# 14_Clocks.net
KiCad netlist of a schematic drawn in Altium Designer
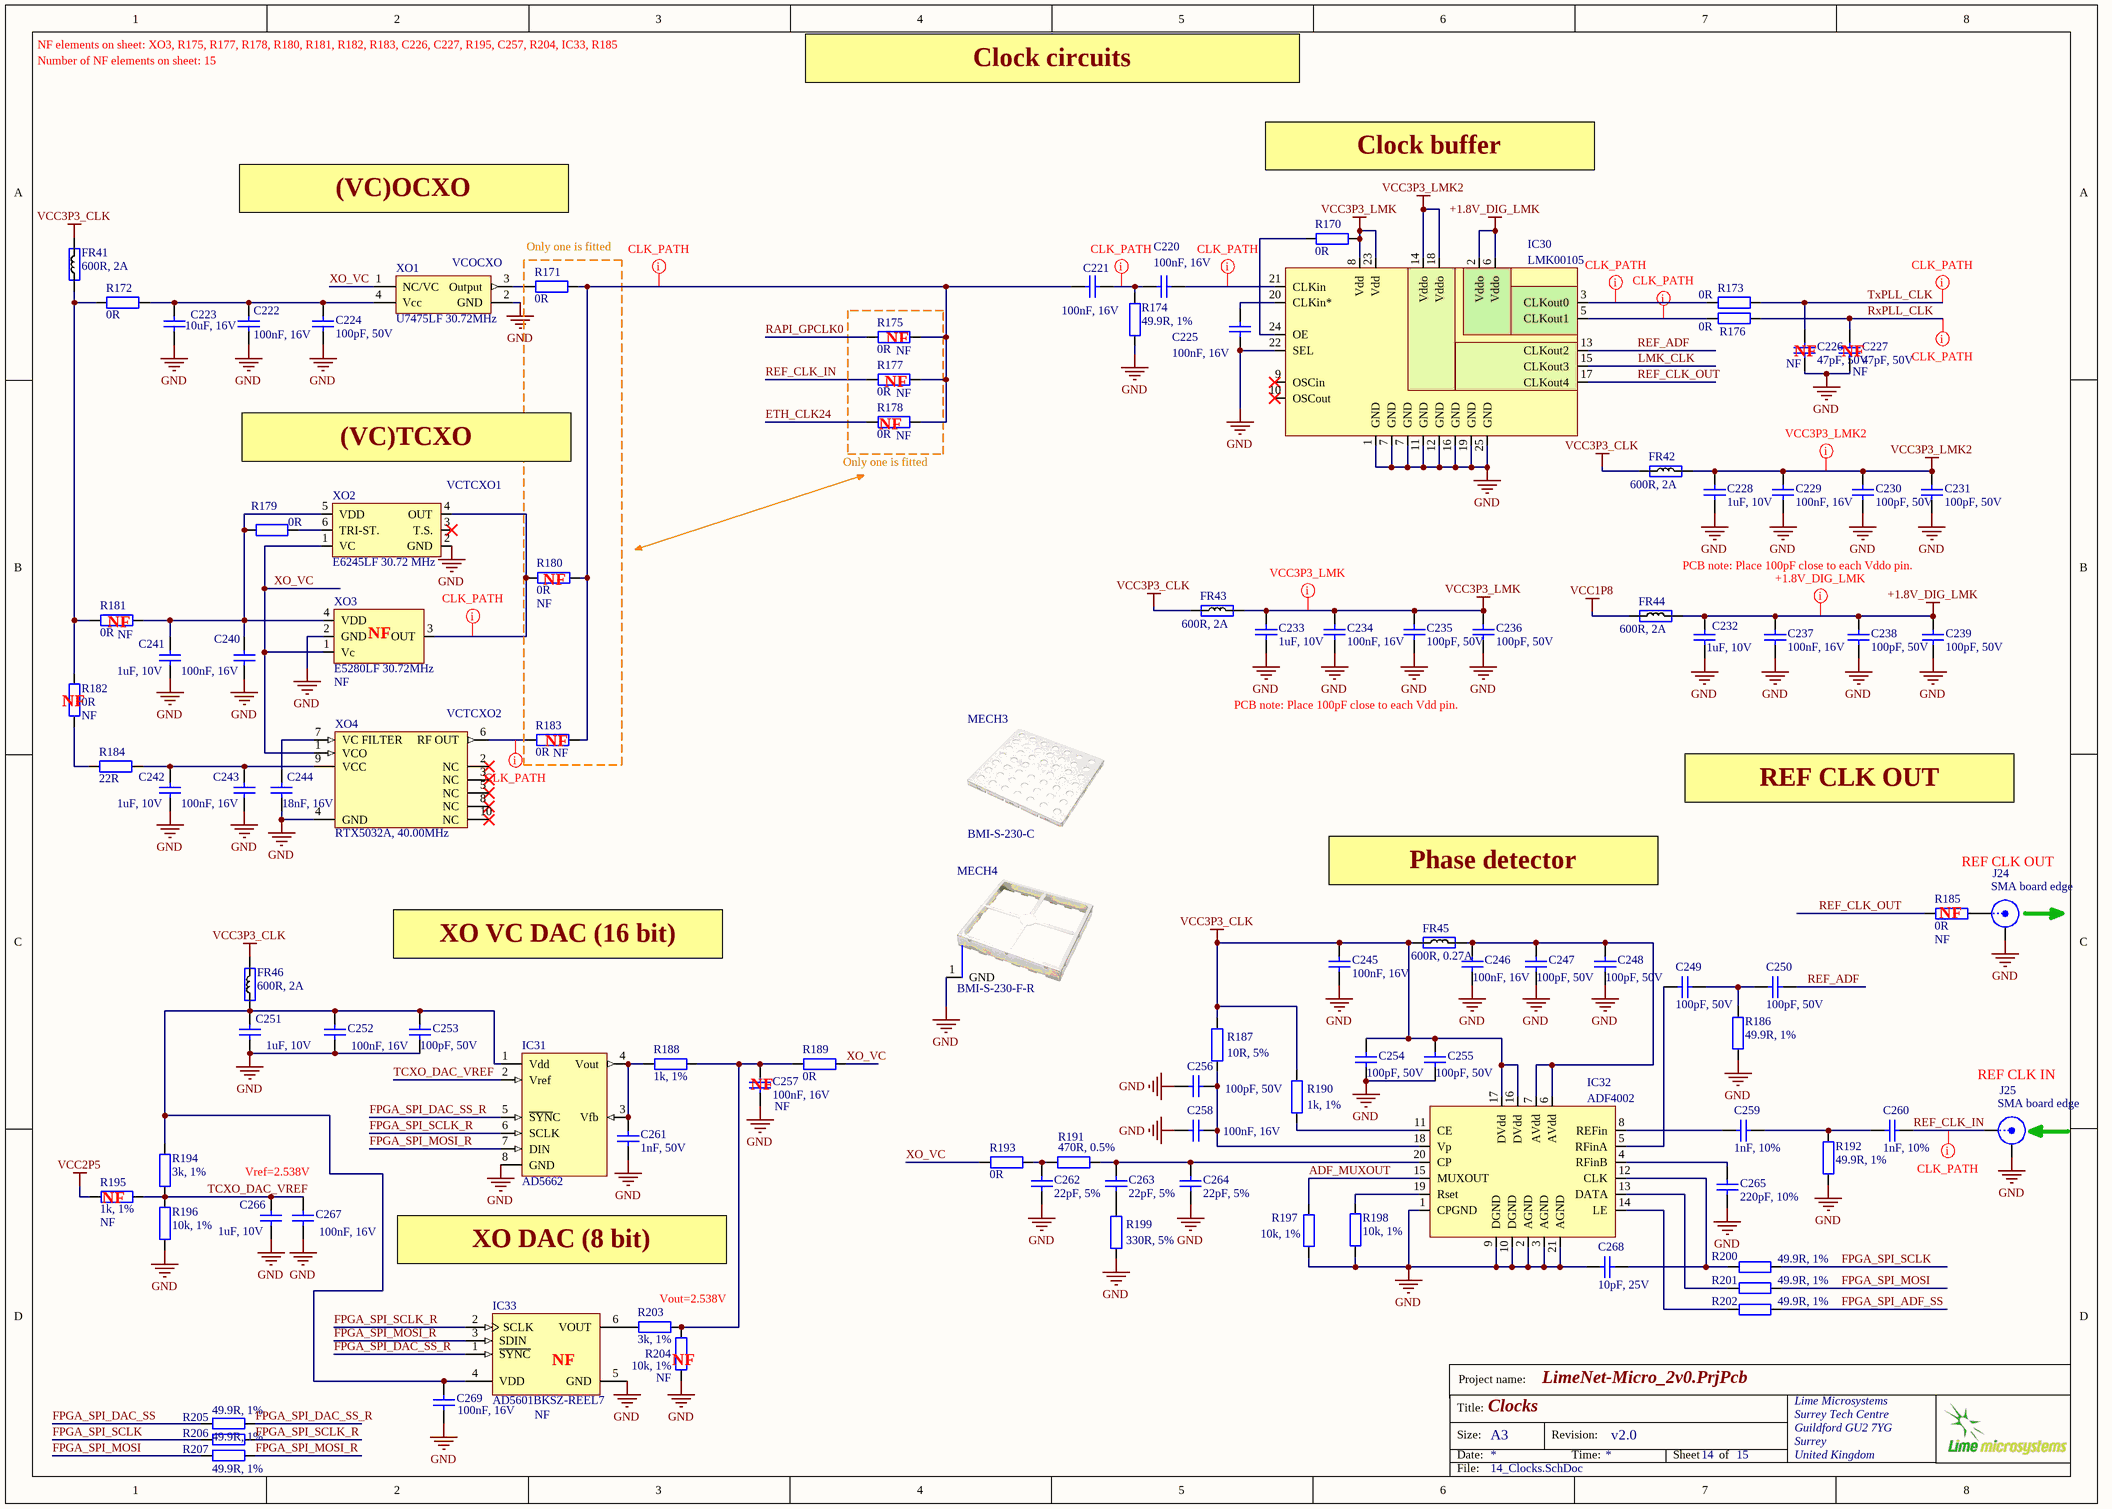
[diagram p0: 14_Clocks.SchDoc]

(export (version "E")
  (design (tool "Eeschema 10.0.6"))
  (components
    (comp (ref "C220")
      (value "100nF, 16V")
      (footprint "CAP0402")
      (fields
        (field (name "MANUFACTURER") "Murata Electronics")
        (field (name "TOLERANCE") "10 %")
        (field (name "MANUFACTURER PART NUMBER") "GRM155R71C104KA88D")
      )
      (libsource (lib "LimeMicroAltiumLib_schLib") (part "Cap_0402"))
    )
    (comp (ref "C221")
      (value "100nF, 16V")
      (footprint "CAP0402")
      (fields
        (field (name "MANUFACTURER") "Murata Electronics")
        (field (name "TOLERANCE") "10 %")
        (field (name "MANUFACTURER PART NUMBER") "GRM155R71C104KA88D")
      )
      (libsource (lib "LimeMicroAltiumLib_schLib") (part "Cap_0402"))
    )
    (comp (ref "C222")
      (value "100nF, 16V")
      (footprint "CAP0402")
      (fields
        (field (name "MANUFACTURER") "Murata Electronics")
        (field (name "TOLERANCE") "10 %")
        (field (name "MANUFACTURER PART NUMBER") "GRM155R71C104KA88D")
      )
      (libsource (lib "LimeMicroAltiumLib_schLib") (part "Cap_0402"))
    )
    (comp (ref "C223")
      (value "10uF, 16V")
      (footprint "CAP0603")
      (fields (field (name "MANUFACTURER") "Yageo") (field (name "TOLERANCE") "±20%"))
      (libsource (lib "LimeMicroAltiumLib_schLib") (part "Cap_0603"))
    )
    (comp (ref "C224")
      (value "100pF, 50V")
      (footprint "CAP0402")
      (fields (field (name "TOLERANCE") "±5%") (field (name "MANUFACTURER") "Yageo"))
      (libsource (lib "LimeMicroAltiumLib_schLib") (part "Cap_0402"))
    )
    (comp (ref "C225")
      (value "100nF, 16V")
      (footprint "CAP0402")
      (fields
        (field (name "MANUFACTURER") "Murata Electronics")
        (field (name "TOLERANCE") "10 %")
        (field (name "MANUFACTURER PART NUMBER") "GRM155R71C104KA88D")
      )
      (libsource (lib "LimeMicroAltiumLib_schLib") (part "Cap_0402"))
    )
    (comp (ref "C226")
      (value "47pF, 50V")
      (footprint "CAP0402")
      (fields
        (field (name "TOLERANCE") "±1%")
        (field (name "MANUFACTURER") "TDK Corporation")
        (field (name "ASSEMBLY INFO") "NF")
      )
      (libsource (lib "LimeMicroAltiumLib_schLib") (part "Cap_0402"))
    )
    (comp (ref "C227")
      (value "47pF, 50V")
      (footprint "CAP0402")
      (fields
        (field (name "TOLERANCE") "±1%")
        (field (name "MANUFACTURER") "TDK Corporation")
        (field (name "ASSEMBLY INFO") "NF")
      )
      (libsource (lib "LimeMicroAltiumLib_schLib") (part "Cap_0402"))
    )
    (comp (ref "C228")
      (value "1uF, 10V")
      (footprint "CAP0402")
      (description "CAP CER 1UF 10V X5R 0402")
      (fields
        (field (name "MANUFACTURER") "Yageo")
        (field (name "MANUFACTURER PART NUMBER") "CC0402MRX5R6BB105")
      )
      (libsource (lib "LimeMicroAltiumLib_schLib") (part "Cap_0402"))
    )
    (comp (ref "C229")
      (value "100nF, 16V")
      (footprint "CAP0402")
      (fields
        (field (name "MANUFACTURER") "Murata Electronics")
        (field (name "TOLERANCE") "10 %")
        (field (name "MANUFACTURER PART NUMBER") "GRM155R71C104KA88D")
      )
      (libsource (lib "LimeMicroAltiumLib_schLib") (part "Cap_0402"))
    )
    (comp (ref "C230")
      (value "100pF, 50V")
      (footprint "CAP0402")
      (fields (field (name "MANUFACTURER") "Yageo") (field (name "TOLERANCE") "±5%"))
      (libsource (lib "LimeMicroAltiumLib_schLib") (part "Cap_0402"))
    )
    (comp (ref "C231")
      (value "100pF, 50V")
      (footprint "CAP0402")
      (fields (field (name "MANUFACTURER") "Yageo") (field (name "TOLERANCE") "±5%"))
      (libsource (lib "LimeMicroAltiumLib_schLib") (part "Cap_0402"))
    )
    (comp (ref "C232")
      (value "1uF, 10V")
      (footprint "CAP0402")
      (description "CAP CER 1UF 10V X5R 0402")
      (fields
        (field (name "MANUFACTURER") "Yageo")
        (field (name "MANUFACTURER PART NUMBER") "CC0402MRX5R6BB105")
      )
      (libsource (lib "LimeMicroAltiumLib_schLib") (part "Cap_0402"))
    )
    (comp (ref "C233")
      (value "1uF, 10V")
      (footprint "CAP0402")
      (description "CAP CER 1UF 10V X5R 0402")
      (fields
        (field (name "MANUFACTURER") "Yageo")
        (field (name "MANUFACTURER PART NUMBER") "CC0402MRX5R6BB105")
      )
      (libsource (lib "LimeMicroAltiumLib_schLib") (part "Cap_0402"))
    )
    (comp (ref "C234")
      (value "100nF, 16V")
      (footprint "CAP0402")
      (fields
        (field (name "MANUFACTURER") "Murata Electronics")
        (field (name "TOLERANCE") "10 %")
        (field (name "MANUFACTURER PART NUMBER") "GRM155R71C104KA88D")
      )
      (libsource (lib "LimeMicroAltiumLib_schLib") (part "Cap_0402"))
    )
    (comp (ref "C235")
      (value "100pF, 50V")
      (footprint "CAP0402")
      (fields (field (name "MANUFACTURER") "Yageo") (field (name "TOLERANCE") "±5%"))
      (libsource (lib "LimeMicroAltiumLib_schLib") (part "Cap_0402"))
    )
    (comp (ref "C236")
      (value "100pF, 50V")
      (footprint "CAP0402")
      (fields (field (name "MANUFACTURER") "Yageo") (field (name "TOLERANCE") "±5%"))
      (libsource (lib "LimeMicroAltiumLib_schLib") (part "Cap_0402"))
    )
    (comp (ref "C237")
      (value "100nF, 16V")
      (footprint "CAP0402")
      (fields
        (field (name "MANUFACTURER") "Murata Electronics")
        (field (name "TOLERANCE") "10 %")
        (field (name "MANUFACTURER PART NUMBER") "GRM155R71C104KA88D")
      )
      (libsource (lib "LimeMicroAltiumLib_schLib") (part "Cap_0402"))
    )
    (comp (ref "C238")
      (value "100pF, 50V")
      (footprint "CAP0402")
      (fields (field (name "MANUFACTURER") "Yageo") (field (name "TOLERANCE") "±5%"))
      (libsource (lib "LimeMicroAltiumLib_schLib") (part "Cap_0402"))
    )
    (comp (ref "C239")
      (value "100pF, 50V")
      (footprint "CAP0402")
      (fields (field (name "MANUFACTURER") "Yageo") (field (name "TOLERANCE") "±5%"))
      (libsource (lib "LimeMicroAltiumLib_schLib") (part "Cap_0402"))
    )
    (comp (ref "C240")
      (value "100nF, 16V")
      (footprint "CAP0402")
      (fields
        (field (name "MANUFACTURER") "Murata Electronics")
        (field (name "TOLERANCE") "10 %")
        (field (name "MANUFACTURER PART NUMBER") "GRM155R71C104KA88D")
      )
      (libsource (lib "LimeMicroAltiumLib_schLib") (part "Cap_0402"))
    )
    (comp (ref "C241")
      (value "1uF, 10V")
      (footprint "CAP0402")
      (description "CAP CER 1UF 10V X5R 0402")
      (fields
        (field (name "MANUFACTURER") "Yageo")
        (field (name "MANUFACTURER PART NUMBER") "CC0402MRX5R6BB105")
      )
      (libsource (lib "LimeMicroAltiumLib_schLib") (part "Cap_0402"))
    )
    (comp (ref "C242")
      (value "1uF, 10V")
      (footprint "CAP0402")
      (description "CAP CER 1UF 10V X5R 0402")
      (fields
        (field (name "MANUFACTURER") "Yageo")
        (field (name "MANUFACTURER PART NUMBER") "CC0402MRX5R6BB105")
      )
      (libsource (lib "LimeMicroAltiumLib_schLib") (part "Cap_0402"))
    )
    (comp (ref "C243")
      (value "100nF, 16V")
      (footprint "CAP0402")
      (fields
        (field (name "MANUFACTURER") "Murata Electronics")
        (field (name "TOLERANCE") "10 %")
        (field (name "MANUFACTURER PART NUMBER") "GRM155R71C104KA88D")
      )
      (libsource (lib "LimeMicroAltiumLib_schLib") (part "Cap_0402"))
    )
    (comp (ref "C244")
      (value "18nF, 16V")
      (footprint "CAP0402")
      (fields (field (name "MANUFACTURER") "Yageo") (field (name "TOLERANCE") "±10%"))
      (libsource (lib "LimeMicroAltiumLib_schLib") (part "Cap_0402"))
    )
    (comp (ref "C245")
      (value "100nF, 16V")
      (footprint "CAP0402")
      (fields
        (field (name "MANUFACTURER") "Murata Electronics")
        (field (name "TOLERANCE") "10 %")
        (field (name "MANUFACTURER PART NUMBER") "GRM155R71C104KA88D")
      )
      (libsource (lib "LimeMicroAltiumLib_schLib") (part "Cap_0402"))
    )
    (comp (ref "C246")
      (value "100nF, 16V")
      (footprint "CAP0402")
      (fields
        (field (name "MANUFACTURER") "Murata Electronics")
        (field (name "TOLERANCE") "10 %")
        (field (name "MANUFACTURER PART NUMBER") "GRM155R71C104KA88D")
      )
      (libsource (lib "LimeMicroAltiumLib_schLib") (part "Cap_0402"))
    )
    (comp (ref "C247")
      (value "100pF, 50V")
      (footprint "CAP0402")
      (fields (field (name "MANUFACTURER") "Yageo") (field (name "TOLERANCE") "±5%"))
      (libsource (lib "LimeMicroAltiumLib_schLib") (part "Cap_0402"))
    )
    (comp (ref "C248")
      (value "100pF, 50V")
      (footprint "CAP0402")
      (fields (field (name "MANUFACTURER") "Yageo") (field (name "TOLERANCE") "±5%"))
      (libsource (lib "LimeMicroAltiumLib_schLib") (part "Cap_0402"))
    )
    (comp (ref "C249")
      (value "100pF, 50V")
      (footprint "CAP0402")
      (fields (field (name "MANUFACTURER") "Yageo") (field (name "TOLERANCE") "±5%"))
      (libsource (lib "LimeMicroAltiumLib_schLib") (part "Cap_0402"))
    )
    (comp (ref "C250")
      (value "100pF, 50V")
      (footprint "CAP0402")
      (fields (field (name "MANUFACTURER") "Yageo") (field (name "TOLERANCE") "±5%"))
      (libsource (lib "LimeMicroAltiumLib_schLib") (part "Cap_0402"))
    )
    (comp (ref "C251")
      (value "1uF, 10V")
      (footprint "CAP0402")
      (description "CAP CER 1UF 10V X5R 0402")
      (fields
        (field (name "MANUFACTURER") "Yageo")
        (field (name "MANUFACTURER PART NUMBER") "CC0402MRX5R6BB105")
      )
      (libsource (lib "LimeMicroAltiumLib_schLib") (part "Cap_0402"))
    )
    (comp (ref "C252")
      (value "100nF, 16V")
      (footprint "CAP0402")
      (fields
        (field (name "TOLERANCE") "10 %")
        (field (name "MANUFACTURER") "Murata Electronics")
        (field (name "MANUFACTURER PART NUMBER") "GRM155R71C104KA88D")
      )
      (libsource (lib "LimeFPGAboard_schLib") (part "Cap_0603"))
    )
    (comp (ref "C253")
      (value "100pF, 50V")
      (footprint "CAP0402")
      (fields (field (name "MANUFACTURER") "Yageo") (field (name "TOLERANCE") "±5%"))
      (libsource (lib "LimeMicroAltiumLib_schLib") (part "Cap_0402"))
    )
    (comp (ref "C254")
      (value "100pF, 50V")
      (footprint "CAP0402")
      (fields (field (name "MANUFACTURER") "Yageo") (field (name "TOLERANCE") "±5%"))
      (libsource (lib "LimeMicroAltiumLib_schLib") (part "Cap_0402"))
    )
    (comp (ref "C255")
      (value "100pF, 50V")
      (footprint "CAP0402")
      (fields (field (name "MANUFACTURER") "Yageo") (field (name "TOLERANCE") "±5%"))
      (libsource (lib "LimeMicroAltiumLib_schLib") (part "Cap_0402"))
    )
    (comp (ref "C256")
      (value "100pF, 50V")
      (footprint "CAP0402")
      (fields (field (name "MANUFACTURER") "Yageo") (field (name "TOLERANCE") "±5%"))
      (libsource (lib "LimeMicroAltiumLib_schLib") (part "Cap_0402"))
    )
    (comp (ref "C257")
      (value "100nF, 16V")
      (footprint "CAP0402")
      (fields
        (field (name "ASSEMBLY INFO") "NF")
        (field (name "MANUFACTURER") "Murata Electronics")
        (field (name "TOLERANCE") "10 %")
        (field (name "MANUFACTURER PART NUMBER") "GRM155R71C104KA88D")
      )
      (libsource (lib "LimeMicroAltiumLib_schLib") (part "Cap_0402"))
    )
    (comp (ref "C258")
      (value "100nF, 16V")
      (footprint "CAP0402")
      (fields
        (field (name "MANUFACTURER") "Murata Electronics")
        (field (name "TOLERANCE") "10 %")
        (field (name "MANUFACTURER PART NUMBER") "GRM155R71C104KA88D")
      )
      (libsource (lib "LimeMicroAltiumLib_schLib") (part "Cap_0402"))
    )
    (comp (ref "C259")
      (value "1nF, 10%")
      (footprint "CAP0402")
      (fields (field (name "TOLERANCE") "10 %") (field (name "MANUFACTURER") "Murata Electronics"))
      (libsource (lib "LimeMicroAltiumLib_schLib") (part "Cap_0402"))
    )
    (comp (ref "C260")
      (value "1nF, 10%")
      (footprint "CAP0402")
      (fields (field (name "TOLERANCE") "10 %") (field (name "MANUFACTURER") "Murata Electronics"))
      (libsource (lib "LimeMicroAltiumLib_schLib") (part "Cap_0402"))
    )
    (comp (ref "C261")
      (value "1nF, 50V")
      (footprint "CAP0402")
      (fields
        (field (name "TOLERANCE") "±10%")
        (field (name "MANUFACTURER") "Murata Electronics North America")
      )
      (libsource (lib "LimeMicroAltiumLib_schLib") (part "Cap_0402"))
    )
    (comp (ref "C262")
      (value "22pF, 5%")
      (footprint "CAP0402")
      (fields (field (name "TOLERANCE") "±5%") (field (name "MANUFACTURER") "Yageo"))
      (libsource (lib "LimeMicroAltiumLib_schLib") (part "Cap_0402"))
    )
    (comp (ref "C263")
      (value "22pF, 5%")
      (footprint "CAP0402")
      (fields (field (name "TOLERANCE") "±5%") (field (name "MANUFACTURER") "Yageo"))
      (libsource (lib "LimeMicroAltiumLib_schLib") (part "Cap_0402"))
    )
    (comp (ref "C264")
      (value "22pF, 5%")
      (footprint "CAP0402")
      (fields (field (name "TOLERANCE") "±5%") (field (name "MANUFACTURER") "Yageo"))
      (libsource (lib "LimeMicroAltiumLib_schLib") (part "Cap_0402"))
    )
    (comp (ref "C265")
      (value "220pF, 10%")
      (footprint "CAP0402")
      (fields (field (name "MANUFACTURER") "Yageo") (field (name "TOLERANCE") "±10%"))
      (libsource (lib "LimeMicroAltiumLib_schLib") (part "Cap_0402"))
    )
    (comp (ref "C266")
      (value "1uF, 10V")
      (footprint "CAP0402")
      (description "CAP CER 1UF 10V X5R 0402")
      (fields
        (field (name "MANUFACTURER") "Yageo")
        (field (name "MANUFACTURER PART NUMBER") "CC0402MRX5R6BB105")
      )
      (libsource (lib "LimeMicroAltiumLib_schLib") (part "Cap_0402"))
    )
    (comp (ref "C267")
      (value "100nF, 16V")
      (footprint "CAP0402")
      (fields
        (field (name "TOLERANCE") "10 %")
        (field (name "MANUFACTURER") "Murata Electronics")
        (field (name "MANUFACTURER PART NUMBER") "GRM155R71C104KA88D")
      )
      (libsource (lib "LimeFPGAboard_schLib") (part "Cap_0603"))
    )
    (comp (ref "C268")
      (value "10pF, 25V")
      (footprint "CAP0402")
      (fields (field (name "MANUFACTURER") "AVX"))
      (libsource (lib "LimeMicroAltiumLib_schLib") (part "Cap_0402"))
    )
    (comp (ref "C269")
      (value "100nF, 16V")
      (footprint "CAP0402")
      (fields
        (field (name "TOLERANCE") "10 %")
        (field (name "MANUFACTURER") "Murata Electronics")
        (field (name "MANUFACTURER PART NUMBER") "GRM155R71C104KA88D")
      )
      (libsource (lib "LimeFPGAboard_schLib") (part "Cap_0603"))
    )
    (comp (ref "FR41")
      (value "600R, 2A")
      (footprint "RES0805")
      (fields (field (name "MANUFACTURER") "TDK Corporation"))
      (libsource (lib "LimeFPGAboard_schLib") (part "Ferrite"))
    )
    (comp (ref "FR42")
      (value "600R, 2A")
      (footprint "RES0805")
      (fields (field (name "MANUFACTURER") "TDK Corporation"))
      (libsource (lib "LimeMicroAltiumLib_schLib") (part "Ferrite"))
    )
    (comp (ref "FR43")
      (value "600R, 2A")
      (footprint "RES0805")
      (fields (field (name "MANUFACTURER") "TDK Corporation"))
      (libsource (lib "LimeMicroAltiumLib_schLib") (part "Ferrite"))
    )
    (comp (ref "FR44")
      (value "600R, 2A")
      (footprint "RES0805")
      (fields (field (name "MANUFACTURER") "TDK Corporation"))
      (libsource (lib "LimeMicroAltiumLib_schLib") (part "Ferrite"))
    )
    (comp (ref "FR45")
      (value "600R, 0.27A")
      (footprint "RES0201")
      (fields (field (name "MANUFACTURER") "Taiyo Yuden"))
      (libsource (lib "LimeMicroAltiumLib_schLib") (part "Ferrite"))
    )
    (comp (ref "FR46")
      (value "600R, 2A")
      (footprint "RES0805")
      (fields (field (name "MANUFACTURER") "TDK Corporation"))
      (libsource (lib "LimeMicroAltiumLib_schLib") (part "Ferrite"))
    )
    (comp (ref "IC30")
      (value "LMK00105")
      (footprint "LMK00105SQ")
      (fields (field (name "MANUFACTURER") "Texas Instruments"))
      (libsource (lib "LimeMicroAltiumLib_schLib") (part "LMK00105"))
    )
    (comp (ref "IC31")
      (value "AD5662")
      (footprint "AD5662_SOT23-8")
      (fields (field (name "MANUFACTURER") "Analog Devices Inc."))
      (libsource (lib "LimeMicroAltiumLib_schLib") (part "AD5662"))
    )
    (comp (ref "IC32")
      (value "ADF4002")
      (footprint "ADF4002")
      (fields (field (name "MANUFACTURER") "Analog Devices Inc"))
      (libsource (lib "LimeMicroAltiumLib_schLib") (part "ADF4002"))
    )
    (comp (ref "IC33")
      (value "AD5601BKSZ-REEL7")
      (footprint "AD5601_SOT23-6")
      (fields
        (field (name "GENERIC PART NUMBER") "AD5601")
        (field (name "MANUFACTURER") "Analog Devices")
        (field (name "ASSEMBLY INFO") "NF")
      )
      (libsource (lib "LimeMicroAltiumLib_schLib") (part "AD5601BKSZ-REEL7"))
    )
    (comp (ref "J24")
      (value "SMA board edge")
      (footprint "SMA_connector_board_edge_SM")
      (description "CONN SMA JACK STR 50OHM EDGE MNT")
      (fields (field (name "MANUFACTURER") "RF Solutions"))
      (libsource (lib "LimeMicroAltiumLib_schLib") (part "RF_IF_connector"))
    )
    (comp (ref "J25")
      (value "SMA board edge")
      (footprint "SMA_connector_board_edge_SM")
      (description "CONN SMA JACK STR 50OHM EDGE MNT")
      (fields (field (name "MANUFACTURER") "RF Solutions"))
      (libsource (lib "LimeMicroAltiumLib_schLib") (part "RF_IF_connector"))
    )
    (comp (ref "MECH3")
      (value "BMI-S-230-C")
      (fields (field (name "MANUFACTURER") "Laird Technologies EMI"))
      (libsource (lib "LimeMicroAltiumLib_schLib_r01") (part "RFI_SHIELD_2_cover"))
    )
    (comp (ref "MECH4")
      (value "BMI-S-230-F-R")
      (footprint "RFI_SHIELD_BMI-S-230-F-R")
      (fields (field (name "MANUFACTURER") "Laird Technologies EMI"))
      (libsource (lib "LimeMicroAltiumLib_schLib_r01") (part "RFI_SHIELD_2_frame"))
    )
    (comp (ref "R170")
      (value "0R")
      (footprint "RES0402")
      (fields (field (name "MANUFACTURER") "Yageo") (field (name "TOLERANCE") "Jumper"))
      (libsource (lib "LimeMicroAltiumLib_schLib") (part "Res_0402"))
    )
    (comp (ref "R171")
      (value "0R")
      (footprint "RES0402_v2")
      (fields (field (name "MANUFACTURER") "Yageo") (field (name "TOLERANCE") "Jumper"))
      (libsource (lib "LimeMicroAltiumLib_schLib") (part "Res_0402"))
    )
    (comp (ref "R172")
      (value "0R")
      (footprint "RES0402")
      (fields (field (name "MANUFACTURER") "Yageo") (field (name "TOLERANCE") "Jumper"))
      (libsource (lib "LimeMicroAltiumLib_schLib") (part "Res_0402"))
    )
    (comp (ref "R173")
      (value "0R")
      (footprint "RES0402")
      (fields (field (name "MANUFACTURER") "Yageo") (field (name "TOLERANCE") "Jumper"))
      (libsource (lib "LimeMicroAltiumLib_schLib") (part "Res_0402"))
    )
    (comp (ref "R174")
      (value "49.9R, 1%")
      (footprint "RES0402")
      (fields
        (field (name "TOLERANCE") "±1%")
        (field (name "MANUFACTURER") "Samsung Electro-Mechanics America, Inc.")
        (field (name "MANUFACTURER PART NUMBER") "RC1005F49R9CS")
      )
      (libsource (lib "LimeMicroAltiumLib_schLib") (part "Res_0402"))
    )
    (comp (ref "R175")
      (value "0R")
      (footprint "RES0402_v2")
      (fields
        (field (name "ASSEMBLY INFO") "NF")
        (field (name "MANUFACTURER") "Yageo")
        (field (name "TOLERANCE") "Jumper")
      )
      (libsource (lib "LimeMicroAltiumLib_schLib") (part "Res_0402"))
    )
    (comp (ref "R176")
      (value "0R")
      (footprint "RES0402")
      (fields (field (name "MANUFACTURER") "Yageo") (field (name "TOLERANCE") "Jumper"))
      (libsource (lib "LimeMicroAltiumLib_schLib") (part "Res_0402"))
    )
    (comp (ref "R177")
      (value "0R")
      (footprint "RES0402_v2")
      (fields
        (field (name "ASSEMBLY INFO") "NF")
        (field (name "MANUFACTURER") "Yageo")
        (field (name "TOLERANCE") "Jumper")
      )
      (libsource (lib "LimeMicroAltiumLib_schLib") (part "Res_0402"))
    )
    (comp (ref "R178")
      (value "0R")
      (footprint "RES0402_v2")
      (fields
        (field (name "ASSEMBLY INFO") "NF")
        (field (name "MANUFACTURER") "Yageo")
        (field (name "TOLERANCE") "Jumper")
      )
      (libsource (lib "LimeMicroAltiumLib_schLib") (part "Res_0402"))
    )
    (comp (ref "R179")
      (value "0R")
      (footprint "RES0402")
      (fields (field (name "MANUFACTURER") "Yageo") (field (name "TOLERANCE") "Jumper"))
      (libsource (lib "LimeMicroAltiumLib_schLib") (part "Res_0402"))
    )
    (comp (ref "R180")
      (value "0R")
      (footprint "RES0402_v2")
      (fields
        (field (name "ASSEMBLY INFO") "NF")
        (field (name "MANUFACTURER") "Yageo")
        (field (name "TOLERANCE") "Jumper")
      )
      (libsource (lib "LimeMicroAltiumLib_schLib") (part "Res_0402"))
    )
    (comp (ref "R181")
      (value "0R")
      (footprint "RES0402")
      (fields
        (field (name "MANUFACTURER") "Yageo")
        (field (name "TOLERANCE") "Jumper")
        (field (name "ASSEMBLY INFO") "NF")
      )
      (libsource (lib "") (part "Res_0402_1"))
    )
    (comp (ref "R182")
      (value "0R")
      (footprint "RES0402")
      (fields
        (field (name "ASSEMBLY INFO") "NF")
        (field (name "MANUFACTURER") "Yageo")
        (field (name "TOLERANCE") "Jumper")
      )
      (libsource (lib "LimeMicroAltiumLib_schLib") (part "Res_0402"))
    )
    (comp (ref "R183")
      (value "0R")
      (footprint "RES0402_v2")
      (fields
        (field (name "ASSEMBLY INFO") "NF")
        (field (name "MANUFACTURER") "Yageo")
        (field (name "TOLERANCE") "Jumper")
      )
      (libsource (lib "LimeMicroAltiumLib_schLib") (part "Res_0402"))
    )
    (comp (ref "R184")
      (value "22R")
      (footprint "RES0402")
      (fields (field (name "TOLERANCE") "±1%") (field (name "MANUFACTURER") "Yageo"))
      (libsource (lib "LimeFPGAboard_schLib") (part "Res_0402"))
    )
    (comp (ref "R185")
      (value "0R")
      (footprint "RES0402")
      (fields
        (field (name "ASSEMBLY INFO") "NF")
        (field (name "MANUFACTURER") "Yageo")
        (field (name "TOLERANCE") "Jumper")
      )
      (libsource (lib "LimeMicroAltiumLib_schLib") (part "Res_0402"))
    )
    (comp (ref "R186")
      (value "49.9R, 1%")
      (footprint "RES0402")
      (fields
        (field (name "TOLERANCE") "±1%")
        (field (name "MANUFACTURER") "Samsung Electro-Mechanics America, Inc.")
        (field (name "MANUFACTURER PART NUMBER") "RC1005F49R9CS")
      )
      (libsource (lib "LimeMicroAltiumLib_schLib") (part "Res_0402"))
    )
    (comp (ref "R187")
      (value "10R, 5%")
      (footprint "RES0402")
      (fields (field (name "TOLERANCE") "±5%") (field (name "MANUFACTURER") "Yageo"))
      (libsource (lib "LimeMicroAltiumLib_schLib") (part "Res_0402"))
    )
    (comp (ref "R188")
      (value "1k, 1%")
      (footprint "RES0402")
      (fields (field (name "MANUFACTURER") "Stackpole Electronics Inc") (field (name "TOLERANCE") "±1%"))
      (libsource (lib "LimeMicroAltiumLib_schLib") (part "Res_0402"))
    )
    (comp (ref "R189")
      (value "0R")
      (footprint "RES0402")
      (fields (field (name "MANUFACTURER") "Yageo") (field (name "TOLERANCE") "Jumper"))
      (libsource (lib "LimeMicroAltiumLib_schLib") (part "Res_0402"))
    )
    (comp (ref "R190")
      (value "1k, 1%")
      (footprint "RES0402")
      (fields (field (name "MANUFACTURER") "Stackpole Electronics Inc") (field (name "TOLERANCE") "±1%"))
      (libsource (lib "LimeMicroAltiumLib_schLib") (part "Res_0402"))
    )
    (comp (ref "R191")
      (value "470R, 0.5%")
      (footprint "RES0402")
      (fields
        (field (name "TOLERANCE") "±0.5%")
        (field (name "MANUFACTURER") "Panasonic Electronic Components")
      )
      (libsource (lib "LimeMicroAltiumLib_schLib") (part "Res_0402"))
    )
    (comp (ref "R192")
      (value "49.9R, 1%")
      (footprint "RES0402")
      (fields
        (field (name "TOLERANCE") "±1%")
        (field (name "MANUFACTURER") "Samsung Electro-Mechanics America, Inc.")
        (field (name "MANUFACTURER PART NUMBER") "RC1005F49R9CS")
      )
      (libsource (lib "LimeMicroAltiumLib_schLib") (part "Res_0402"))
    )
    (comp (ref "R193")
      (value "0R")
      (footprint "RES0402")
      (fields (field (name "MANUFACTURER") "Yageo") (field (name "TOLERANCE") "Jumper"))
      (libsource (lib "LimeMicroAltiumLib_schLib") (part "Res_0402"))
    )
    (comp (ref "R194")
      (value "3k, 1%")
      (footprint "RES0402")
      (fields (field (name "TOLERANCE") "±1%") (field (name "MANUFACTURER") "Vishay Dale"))
      (libsource (lib "LimeMicroAltiumLib_schLib") (part "Res_0402"))
    )
    (comp (ref "R195")
      (value "1k, 1%")
      (footprint "RES0402")
      (fields
        (field (name "ASSEMBLY INFO") "NF")
        (field (name "MANUFACTURER") "Stackpole Electronics Inc")
        (field (name "TOLERANCE") "±1%")
      )
      (libsource (lib "LimeMicroAltiumLib_schLib") (part "Res_0402"))
    )
    (comp (ref "R196")
      (value "10k, 1%")
      (footprint "RES0402")
      (fields (field (name "MANUFACTURER") "Yageo") (field (name "TOLERANCE") "±1%"))
      (libsource (lib "LimeMicroAltiumLib_schLib") (part "Res_0402"))
    )
    (comp (ref "R197")
      (value "10k, 1%")
      (footprint "RES0402")
      (fields (field (name "MANUFACTURER") "Yageo") (field (name "TOLERANCE") "±1%"))
      (libsource (lib "LimeMicroAltiumLib_schLib") (part "Res_0402"))
    )
    (comp (ref "R198")
      (value "10k, 1%")
      (footprint "RES0402")
      (fields (field (name "MANUFACTURER") "Yageo") (field (name "TOLERANCE") "±1%"))
      (libsource (lib "LimeMicroAltiumLib_schLib") (part "Res_0402"))
    )
    (comp (ref "R199")
      (value "330R, 5%")
      (footprint "RES0402")
      (fields (field (name "MANUFACTURER") "Yageo") (field (name "TOLERANCE") "±5%"))
      (libsource (lib "LimeMicroAltiumLib_schLib") (part "Res_0402"))
    )
    (comp (ref "R200")
      (value "49.9R, 1%")
      (footprint "RES0402")
      (fields
        (field (name "TOLERANCE") "±1%")
        (field (name "MANUFACTURER") "Samsung Electro-Mechanics America, Inc.")
        (field (name "MANUFACTURER PART NUMBER") "RC1005F49R9CS")
      )
      (libsource (lib "LimeMicroAltiumLib_schLib") (part "Res_0402"))
    )
    (comp (ref "R201")
      (value "49.9R, 1%")
      (footprint "RES0402")
      (fields
        (field (name "TOLERANCE") "±1%")
        (field (name "MANUFACTURER") "Samsung Electro-Mechanics America, Inc.")
        (field (name "MANUFACTURER PART NUMBER") "RC1005F49R9CS")
      )
      (libsource (lib "LimeMicroAltiumLib_schLib") (part "Res_0402"))
    )
    (comp (ref "R202")
      (value "49.9R, 1%")
      (footprint "RES0402")
      (fields
        (field (name "TOLERANCE") "±1%")
        (field (name "MANUFACTURER") "Samsung Electro-Mechanics America, Inc.")
        (field (name "MANUFACTURER PART NUMBER") "RC1005F49R9CS")
      )
      (libsource (lib "LimeMicroAltiumLib_schLib") (part "Res_0402"))
    )
    (comp (ref "R203")
      (value "3k, 1%")
      (footprint "RES0402")
      (fields (field (name "TOLERANCE") "±1%") (field (name "MANUFACTURER") "Vishay Dale"))
      (libsource (lib "LimeMicroAltiumLib_schLib") (part "Res_0402"))
    )
    (comp (ref "R204")
      (value "10k, 1%")
      (footprint "RES0402")
      (fields
        (field (name "ASSEMBLY INFO") "NF")
        (field (name "MANUFACTURER") "Yageo")
        (field (name "TOLERANCE") "±1%")
      )
      (libsource (lib "LimeMicroAltiumLib_schLib") (part "Res_0402"))
    )
    (comp (ref "R205")
      (value "49.9R, 1%")
      (footprint "RES0402")
      (fields
        (field (name "TOLERANCE") "±1%")
        (field (name "MANUFACTURER") "Samsung Electro-Mechanics America, Inc.")
      )
      (libsource (lib "LimeMicroAltiumLib_schLib") (part "Res_0402"))
    )
    (comp (ref "R206")
      (value "49.9R, 1%")
      (footprint "RES0402")
      (fields
        (field (name "TOLERANCE") "±1%")
        (field (name "MANUFACTURER") "Samsung Electro-Mechanics America, Inc.")
      )
      (libsource (lib "LimeMicroAltiumLib_schLib") (part "Res_0402"))
    )
    (comp (ref "R207")
      (value "49.9R, 1%")
      (footprint "RES0402")
      (fields
        (field (name "TOLERANCE") "±1%")
        (field (name "MANUFACTURER") "Samsung Electro-Mechanics America, Inc.")
      )
      (libsource (lib "LimeMicroAltiumLib_schLib") (part "Res_0402"))
    )
    (comp (ref "XO1")
      (value "U7475LF 30.72MHz")
      (footprint "AOCJYR-10.000MHz")
      (fields (field (name "MANUFACTURER") "Rakon"))
      (libsource (lib "LimeMicroAltiumLib_schLib") (part "AOCJYR-10.000MHz"))
    )
    (comp (ref "XO2")
      (value "E6245LF 30.72 MHz")
      (footprint "RAKON_RPT7050A")
      (fields (field (name "MANUFACTURER") "Rakon"))
      (libsource (lib "LimeMicroAltiumLib_schLib") (part "RPT7050A"))
    )
    (comp (ref "XO3")
      (value "E5280LF 30.72MHz")
      (footprint "RAKON_TXCO")
      (fields (field (name "ASSEMBLY INFO") "NF") (field (name "MANUFACTURER") "Rakon"))
      (libsource (lib "LimeMicroAltiumLib_schLib") (part "TXCO"))
    )
    (comp (ref "XO4")
      (value "RTX5032A, 40.00MHz")
      (footprint "RAKON_RTX5032A")
      (fields (field (name "MANUFACTURER") "Rakon"))
      (libsource (lib "LimeMicroAltiumLib_schLib") (part "Rakon_RTX5032A"))
    )
  )
  (nets
    (net (code "1") (name "+1.8V_DIG_LMK") (class "Default")
      (node (ref "C232") (pin "2") (pinfunction "2_2") (pintype "passive"))
      (node (ref "C237") (pin "2") (pinfunction "2_2") (pintype "passive"))
      (node (ref "C238") (pin "2") (pinfunction "2_2") (pintype "passive"))
      (node (ref "C239") (pin "2") (pinfunction "2_2") (pintype "passive"))
      (node (ref "FR44") (pin "2") (pinfunction "2_2") (pintype "passive"))
      (node (ref "IC30") (pin "2") (pinfunction "Vddo_2") (pintype "passive"))
      (node (ref "IC30") (pin "6") (pinfunction "Vddo_6") (pintype "passive"))
    )
    (net (code "2") (name "/ADF_MUXOUT") (class "Default")
      (node (ref "IC32") (pin "15") (pinfunction "MUXOUT_15") (pintype "passive"))
      (node (ref "R197") (pin "1") (pinfunction "1_1") (pintype "passive"))
    )
    (net (code "3") (name "/ETH_CLK24") (class "Default")
      (node (ref "R178") (pin "2") (pinfunction "2_2") (pintype "passive"))
    )
    (net (code "4") (name "/FPGA_SPI_ADF_SS") (class "Default")
      (node (ref "R202") (pin "1") (pinfunction "1_1") (pintype "passive"))
    )
    (net (code "5") (name "/FPGA_SPI_DAC_SS") (class "Default")
      (node (ref "R205") (pin "2") (pinfunction "2_2") (pintype "passive"))
    )
    (net (code "6") (name "/FPGA_SPI_DAC_SS_R") (class "Default")
      (node (ref "IC31") (pin "5") (pinfunction "~{SYN}C_5") (pintype "input"))
      (node (ref "IC33") (pin "1") (pinfunction "~{SYNC}_1") (pintype "input"))
      (node (ref "R205") (pin "1") (pinfunction "1_1") (pintype "passive"))
    )
    (net (code "7") (name "/FPGA_SPI_MOSI") (class "Default")
      (node (ref "R201") (pin "1") (pinfunction "1_1") (pintype "passive"))
      (node (ref "R207") (pin "2") (pinfunction "2_2") (pintype "passive"))
    )
    (net (code "8") (name "/FPGA_SPI_MOSI_R") (class "Default")
      (node (ref "IC31") (pin "7") (pinfunction "DIN_7") (pintype "input"))
      (node (ref "IC33") (pin "3") (pinfunction "SDIN_3") (pintype "input"))
      (node (ref "R207") (pin "1") (pinfunction "1_1") (pintype "passive"))
    )
    (net (code "9") (name "/FPGA_SPI_SCLK") (class "Default")
      (node (ref "R200") (pin "1") (pinfunction "1_1") (pintype "passive"))
      (node (ref "R206") (pin "2") (pinfunction "2_2") (pintype "passive"))
    )
    (net (code "10") (name "/FPGA_SPI_SCLK_R") (class "Default")
      (node (ref "IC31") (pin "6") (pinfunction "SCLK_6") (pintype "input"))
      (node (ref "IC33") (pin "2") (pinfunction "SCLK_2") (pintype "input"))
      (node (ref "R206") (pin "1") (pinfunction "1_1") (pintype "passive"))
    )
    (net (code "11") (name "/LMK_CLK") (class "Default")
      (node (ref "IC30") (pin "15") (pinfunction "CLKout3_15") (pintype "passive"))
    )
    (net (code "12") (name "/RAPI_GPCLK0") (class "Default")
      (node (ref "R175") (pin "2") (pinfunction "2_2") (pintype "passive"))
    )
    (net (code "13") (name "/REF_ADF") (class "Default")
      (node (ref "C250") (pin "2") (pinfunction "2_2") (pintype "passive"))
      (node (ref "IC30") (pin "13") (pinfunction "CLKout2_13") (pintype "passive"))
    )
    (net (code "14") (name "/REF_CLK_IN") (class "Default")
      (node (ref "C260") (pin "1") (pinfunction "1_1") (pintype "passive"))
      (node (ref "J25") (pin "1") (pinfunction "X_1") (pintype "passive"))
      (node (ref "R177") (pin "2") (pinfunction "2_2") (pintype "passive"))
    )
    (net (code "15") (name "/REF_CLK_OUT") (class "Default")
      (node (ref "IC30") (pin "17") (pinfunction "CLKout4_17") (pintype "passive"))
      (node (ref "R185") (pin "2") (pinfunction "2_2") (pintype "passive"))
    )
    (net (code "16") (name "/RxPLL_CLK") (class "Default")
      (node (ref "C227") (pin "2") (pinfunction "2_2") (pintype "passive"))
      (node (ref "R176") (pin "1") (pinfunction "1_1") (pintype "passive"))
    )
    (net (code "17") (name "/TCXO_DAC_VREF") (class "Default")
      (node (ref "C266") (pin "2") (pinfunction "2_2") (pintype "passive"))
      (node (ref "C267") (pin "1") (pinfunction "1_1") (pintype "passive"))
      (node (ref "IC31") (pin "2") (pinfunction "Vref_2") (pintype "input"))
      (node (ref "R194") (pin "1") (pinfunction "1_1") (pintype "passive"))
      (node (ref "R195") (pin "1") (pinfunction "1_1") (pintype "passive"))
      (node (ref "R196") (pin "1") (pinfunction "1_1") (pintype "passive"))
    )
    (net (code "18") (name "/TxPLL_CLK") (class "Default")
      (node (ref "C226") (pin "2") (pinfunction "2_2") (pintype "passive"))
      (node (ref "R173") (pin "1") (pinfunction "1_1") (pintype "passive"))
    )
    (net (code "19") (name "/XO_VC") (class "Default")
      (node (ref "R189") (pin "1") (pinfunction "1_1") (pintype "passive"))
      (node (ref "R193") (pin "2") (pinfunction "2_2") (pintype "passive"))
      (node (ref "XO1") (pin "1") (pinfunction "NC/VC_1") (pintype "passive"))
      (node (ref "XO2") (pin "1") (pinfunction "VC_1") (pintype "passive"))
      (node (ref "XO3") (pin "1") (pinfunction "Vc_1") (pintype "passive"))
      (node (ref "XO4") (pin "1") (pinfunction "VCO_1") (pintype "input"))
    )
    (net (code "20") (name "GND") (class "Default")
      (node (ref "C222") (pin "1") (pinfunction "1_1") (pintype "passive"))
      (node (ref "C223") (pin "1") (pinfunction "1_1") (pintype "passive"))
      (node (ref "C224") (pin "2") (pinfunction "2_2") (pintype "passive"))
      (node (ref "C225") (pin "1") (pinfunction "1_1") (pintype "passive"))
      (node (ref "C226") (pin "1") (pinfunction "1_1") (pintype "passive"))
      (node (ref "C227") (pin "1") (pinfunction "1_1") (pintype "passive"))
      (node (ref "C228") (pin "1") (pinfunction "1_1") (pintype "passive"))
      (node (ref "C229") (pin "1") (pinfunction "1_1") (pintype "passive"))
      (node (ref "C230") (pin "1") (pinfunction "1_1") (pintype "passive"))
      (node (ref "C231") (pin "1") (pinfunction "1_1") (pintype "passive"))
      (node (ref "C232") (pin "1") (pinfunction "1_1") (pintype "passive"))
      (node (ref "C233") (pin "1") (pinfunction "1_1") (pintype "passive"))
      (node (ref "C234") (pin "1") (pinfunction "1_1") (pintype "passive"))
      (node (ref "C235") (pin "1") (pinfunction "1_1") (pintype "passive"))
      (node (ref "C236") (pin "1") (pinfunction "1_1") (pintype "passive"))
      (node (ref "C237") (pin "1") (pinfunction "1_1") (pintype "passive"))
      (node (ref "C238") (pin "1") (pinfunction "1_1") (pintype "passive"))
      (node (ref "C239") (pin "1") (pinfunction "1_1") (pintype "passive"))
      (node (ref "C240") (pin "1") (pinfunction "1_1") (pintype "passive"))
      (node (ref "C241") (pin "1") (pinfunction "1_1") (pintype "passive"))
      (node (ref "C242") (pin "1") (pinfunction "1_1") (pintype "passive"))
      (node (ref "C243") (pin "1") (pinfunction "1_1") (pintype "passive"))
      (node (ref "C244") (pin "1") (pinfunction "1_1") (pintype "passive"))
      (node (ref "C245") (pin "1") (pinfunction "1_1") (pintype "passive"))
      (node (ref "C246") (pin "1") (pinfunction "1_1") (pintype "passive"))
      (node (ref "C247") (pin "2") (pinfunction "2_2") (pintype "passive"))
      (node (ref "C248") (pin "2") (pinfunction "2_2") (pintype "passive"))
      (node (ref "C251") (pin "1") (pinfunction "1_1") (pintype "passive"))
      (node (ref "C252") (pin "2") (pinfunction "2_2") (pintype "passive"))
      (node (ref "C253") (pin "2") (pinfunction "2_2") (pintype "passive"))
      (node (ref "C254") (pin "2") (pinfunction "2_2") (pintype "passive"))
      (node (ref "C255") (pin "2") (pinfunction "2_2") (pintype "passive"))
      (node (ref "C256") (pin "1") (pinfunction "1_1") (pintype "passive"))
      (node (ref "C257") (pin "1") (pinfunction "1_1") (pintype "passive"))
      (node (ref "C258") (pin "2") (pinfunction "2_2") (pintype "passive"))
      (node (ref "C261") (pin "2") (pinfunction "2_2") (pintype "passive"))
      (node (ref "C262") (pin "1") (pinfunction "1_1") (pintype "passive"))
      (node (ref "C264") (pin "1") (pinfunction "1_1") (pintype "passive"))
      (node (ref "C265") (pin "2") (pinfunction "2_2") (pintype "passive"))
      (node (ref "C266") (pin "1") (pinfunction "1_1") (pintype "passive"))
      (node (ref "C267") (pin "2") (pinfunction "2_2") (pintype "passive"))
      (node (ref "C268") (pin "1") (pinfunction "1_1") (pintype "passive"))
      (node (ref "C269") (pin "2") (pinfunction "2_2") (pintype "passive"))
      (node (ref "IC30") (pin "1") (pinfunction "GND_1") (pintype "passive"))
      (node (ref "IC30") (pin "11") (pinfunction "GND_11") (pintype "passive"))
      (node (ref "IC30") (pin "12") (pinfunction "GND_12") (pintype "passive"))
      (node (ref "IC30") (pin "16") (pinfunction "GND_16") (pintype "passive"))
      (node (ref "IC30") (pin "19") (pinfunction "GND_19") (pintype "passive"))
      (node (ref "IC30") (pin "22") (pinfunction "SEL_22") (pintype "passive"))
      (node (ref "IC30") (pin "25") (pinfunction "GND_25") (pintype "passive"))
      (node (ref "IC30") (pin "7") (pinfunction "GND_7") (pintype "passive"))
      (node (ref "IC31") (pin "8") (pinfunction "GND_8") (pintype "passive"))
      (node (ref "IC32") (pin "1") (pinfunction "CPGND_1") (pintype "passive"))
      (node (ref "IC32") (pin "10") (pinfunction "DGND_10") (pintype "passive"))
      (node (ref "IC32") (pin "2") (pinfunction "AGND_2") (pintype "passive"))
      (node (ref "IC32") (pin "21") (pinfunction "AGND_21") (pintype "passive"))
      (node (ref "IC32") (pin "3") (pinfunction "AGND_3") (pintype "passive"))
      (node (ref "IC32") (pin "9") (pinfunction "DGND_9") (pintype "passive"))
      (node (ref "IC33") (pin "5") (pinfunction "GND_5") (pintype "power_in"))
      (node (ref "J24") (pin "2") (pinfunction "Y_2") (pintype "passive"))
      (node (ref "J25") (pin "2") (pinfunction "Y_2") (pintype "passive"))
      (node (ref "MECH4") (pin "1") (pinfunction "GND_1") (pintype "passive"))
      (node (ref "R174") (pin "1") (pinfunction "1_1") (pintype "passive"))
      (node (ref "R186") (pin "1") (pinfunction "1_1") (pintype "passive"))
      (node (ref "R192") (pin "1") (pinfunction "1_1") (pintype "passive"))
      (node (ref "R196") (pin "2") (pinfunction "2_2") (pintype "passive"))
      (node (ref "R197") (pin "2") (pinfunction "2_2") (pintype "passive"))
      (node (ref "R198") (pin "2") (pinfunction "2_2") (pintype "passive"))
      (node (ref "R199") (pin "1") (pinfunction "1_1") (pintype "passive"))
      (node (ref "R204") (pin "2") (pinfunction "2_2") (pintype "passive"))
      (node (ref "XO1") (pin "2") (pinfunction "GND_2") (pintype "passive"))
      (node (ref "XO2") (pin "2") (pinfunction "GND_2") (pintype "passive"))
      (node (ref "XO3") (pin "2") (pinfunction "GND_2") (pintype "passive"))
      (node (ref "XO4") (pin "4") (pinfunction "GND_4") (pintype "passive"))
    )
    (net (code "21") (name "Net-(C220-Pad2)") (class "Default")
      (node (ref "C220") (pin "2") (pinfunction "2_2") (pintype "passive"))
      (node (ref "C221") (pin "1") (pinfunction "1_1") (pintype "passive"))
      (node (ref "R174") (pin "2") (pinfunction "2_2") (pintype "passive"))
    )
    (net (code "22") (name "Net-(C221-Pad2)") (class "Default")
      (node (ref "C221") (pin "2") (pinfunction "2_2") (pintype "passive"))
      (node (ref "R171") (pin "1") (pinfunction "1_1") (pintype "passive"))
      (node (ref "R175") (pin "1") (pinfunction "1_1") (pintype "passive"))
      (node (ref "R177") (pin "1") (pinfunction "1_1") (pintype "passive"))
      (node (ref "R178") (pin "1") (pinfunction "1_1") (pintype "passive"))
      (node (ref "R180") (pin "1") (pinfunction "1_1") (pintype "passive"))
      (node (ref "R183") (pin "2") (pinfunction "2_2") (pintype "passive"))
    )
    (net (code "23") (name "Net-(C246-Pad2)") (class "Default")
      (node (ref "C246") (pin "2") (pinfunction "2_2") (pintype "passive"))
      (node (ref "C247") (pin "1") (pinfunction "1_1") (pintype "passive"))
      (node (ref "C248") (pin "1") (pinfunction "1_1") (pintype "passive"))
      (node (ref "FR45") (pin "2") (pinfunction "2_2") (pintype "passive"))
      (node (ref "IC32") (pin "6") (pinfunction "AVdd_6") (pintype "passive"))
      (node (ref "IC32") (pin "7") (pinfunction "AVdd_7") (pintype "passive"))
    )
    (net (code "24") (name "Net-(C249-Pad2)") (class "Default")
      (node (ref "C249") (pin "2") (pinfunction "2_2") (pintype "passive"))
      (node (ref "C250") (pin "1") (pinfunction "1_1") (pintype "passive"))
      (node (ref "R186") (pin "2") (pinfunction "2_2") (pintype "passive"))
    )
    (net (code "25") (name "Net-(C257-Pad2)") (class "Default")
      (node (ref "C257") (pin "2") (pinfunction "2_2") (pintype "passive"))
      (node (ref "R188") (pin "1") (pinfunction "1_1") (pintype "passive"))
      (node (ref "R189") (pin "2") (pinfunction "2_2") (pintype "passive"))
      (node (ref "R203") (pin "1") (pinfunction "1_1") (pintype "passive"))
      (node (ref "R204") (pin "1") (pinfunction "1_1") (pintype "passive"))
    )
    (net (code "26") (name "Net-(C259-Pad1)") (class "Default")
      (node (ref "C259") (pin "1") (pinfunction "1_1") (pintype "passive"))
      (node (ref "C260") (pin "2") (pinfunction "2_2") (pintype "passive"))
      (node (ref "R192") (pin "2") (pinfunction "2_2") (pintype "passive"))
    )
    (net (code "27") (name "Net-(C262-Pad2)") (class "Default")
      (node (ref "C262") (pin "2") (pinfunction "2_2") (pintype "passive"))
      (node (ref "R191") (pin "2") (pinfunction "2_2") (pintype "passive"))
      (node (ref "R193") (pin "1") (pinfunction "1_1") (pintype "passive"))
    )
    (net (code "28") (name "Net-(C263-Pad1)") (class "Default")
      (node (ref "C263") (pin "1") (pinfunction "1_1") (pintype "passive"))
      (node (ref "R199") (pin "2") (pinfunction "2_2") (pintype "passive"))
    )
    (net (code "29") (name "Net-(FR41-Pad2)") (class "Default")
      (node (ref "FR41") (pin "2") (pinfunction "2_2") (pintype "passive"))
      (node (ref "R172") (pin "1") (pinfunction "1_1") (pintype "passive"))
      (node (ref "R181") (pin "2") (pinfunction "2_2") (pintype "passive"))
      (node (ref "R182") (pin "1") (pinfunction "1_1") (pintype "passive"))
    )
    (net (code "30") (name "Net-(IC30-CLKin)") (class "Default")
      (node (ref "C220") (pin "1") (pinfunction "1_1") (pintype "passive"))
      (node (ref "IC30") (pin "21") (pinfunction "CLKin_21") (pintype "passive"))
    )
    (net (code "31") (name "Net-(IC30-CLKin*)") (class "Default")
      (node (ref "C225") (pin "2") (pinfunction "2_2") (pintype "passive"))
      (node (ref "IC30") (pin "20") (pinfunction "CLKin*_20") (pintype "passive"))
    )
    (net (code "32") (name "Net-(IC30-CLKout0)") (class "Default")
      (node (ref "IC30") (pin "3") (pinfunction "CLKout0_3") (pintype "passive"))
      (node (ref "R173") (pin "2") (pinfunction "2_2") (pintype "passive"))
    )
    (net (code "33") (name "Net-(IC30-CLKout1)") (class "Default")
      (node (ref "IC30") (pin "5") (pinfunction "CLKout1_5") (pintype "passive"))
      (node (ref "R176") (pin "2") (pinfunction "2_2") (pintype "passive"))
    )
    (net (code "34") (name "Net-(IC30-OE)") (class "Default")
      (node (ref "IC30") (pin "24") (pinfunction "OE_24") (pintype "passive"))
      (node (ref "R170") (pin "1") (pinfunction "1_1") (pintype "passive"))
    )
    (net (code "35") (name "Net-(IC31-Vdd)") (class "Default")
      (node (ref "C251") (pin "2") (pinfunction "2_2") (pintype "passive"))
      (node (ref "C252") (pin "1") (pinfunction "1_1") (pintype "passive"))
      (node (ref "C253") (pin "1") (pinfunction "1_1") (pintype "passive"))
      (node (ref "C269") (pin "1") (pinfunction "1_1") (pintype "passive"))
      (node (ref "FR46") (pin "1") (pinfunction "1_1") (pintype "passive"))
      (node (ref "IC31") (pin "1") (pinfunction "Vdd_1") (pintype "power_in"))
      (node (ref "IC33") (pin "4") (pinfunction "VDD_4") (pintype "power_in"))
      (node (ref "R194") (pin "2") (pinfunction "2_2") (pintype "passive"))
    )
    (net (code "36") (name "Net-(IC31-Vfb)") (class "Default")
      (node (ref "C261") (pin "1") (pinfunction "1_1") (pintype "passive"))
      (node (ref "IC31") (pin "3") (pinfunction "Vfb_3") (pintype "input"))
      (node (ref "IC31") (pin "4") (pinfunction "Vout_4") (pintype "output"))
      (node (ref "R188") (pin "2") (pinfunction "2_2") (pintype "passive"))
    )
    (net (code "37") (name "Net-(IC32-CE)") (class "Default")
      (node (ref "IC32") (pin "11") (pinfunction "CE_11") (pintype "passive"))
      (node (ref "R190") (pin "1") (pinfunction "1_1") (pintype "passive"))
    )
    (net (code "38") (name "Net-(IC32-CLK)") (class "Default")
      (node (ref "C268") (pin "2") (pinfunction "2_2") (pintype "passive"))
      (node (ref "IC32") (pin "12") (pinfunction "CLK_12") (pintype "passive"))
      (node (ref "R200") (pin "2") (pinfunction "2_2") (pintype "passive"))
    )
    (net (code "39") (name "Net-(IC32-CP)") (class "Default")
      (node (ref "C263") (pin "2") (pinfunction "2_2") (pintype "passive"))
      (node (ref "C264") (pin "2") (pinfunction "2_2") (pintype "passive"))
      (node (ref "IC32") (pin "20") (pinfunction "CP_20") (pintype "passive"))
      (node (ref "R191") (pin "1") (pinfunction "1_1") (pintype "passive"))
    )
    (net (code "40") (name "Net-(IC32-DATA)") (class "Default")
      (node (ref "IC32") (pin "13") (pinfunction "DATA_13") (pintype "passive"))
      (node (ref "R201") (pin "2") (pinfunction "2_2") (pintype "passive"))
    )
    (net (code "41") (name "Net-(IC32-LE)") (class "Default")
      (node (ref "IC32") (pin "14") (pinfunction "LE_14") (pintype "passive"))
      (node (ref "R202") (pin "2") (pinfunction "2_2") (pintype "passive"))
    )
    (net (code "42") (name "Net-(IC32-REFin)") (class "Default")
      (node (ref "C259") (pin "2") (pinfunction "2_2") (pintype "passive"))
      (node (ref "IC32") (pin "8") (pinfunction "REFin_8") (pintype "passive"))
    )
    (net (code "43") (name "Net-(IC32-RFinA)") (class "Default")
      (node (ref "C249") (pin "1") (pinfunction "1_1") (pintype "passive"))
      (node (ref "IC32") (pin "5") (pinfunction "RFinA_5") (pintype "passive"))
    )
    (net (code "44") (name "Net-(IC32-RFinB)") (class "Default")
      (node (ref "C265") (pin "1") (pinfunction "1_1") (pintype "passive"))
      (node (ref "IC32") (pin "4") (pinfunction "RFinB_4") (pintype "passive"))
    )
    (net (code "45") (name "Net-(IC32-Rset)") (class "Default")
      (node (ref "IC32") (pin "19") (pinfunction "Rset_19") (pintype "passive"))
      (node (ref "R198") (pin "1") (pinfunction "1_1") (pintype "passive"))
    )
    (net (code "46") (name "Net-(IC32-Vp)") (class "Default")
      (node (ref "C256") (pin "2") (pinfunction "2_2") (pintype "passive"))
      (node (ref "C258") (pin "1") (pinfunction "1_1") (pintype "passive"))
      (node (ref "IC32") (pin "18") (pinfunction "Vp_18") (pintype "passive"))
      (node (ref "R187") (pin "1") (pinfunction "1_1") (pintype "passive"))
    )
    (net (code "47") (name "Net-(IC33-VOUT)") (class "Default")
      (node (ref "IC33") (pin "6") (pinfunction "VOUT_6") (pintype "tri_state"))
      (node (ref "R203") (pin "2") (pinfunction "2_2") (pintype "passive"))
    )
    (net (code "48") (name "Net-(J24-X)") (class "Default")
      (node (ref "J24") (pin "1") (pinfunction "X_1") (pintype "passive"))
      (node (ref "R185") (pin "1") (pinfunction "1_1") (pintype "passive"))
    )
    (net (code "49") (name "Net-(R182-Pad2)") (class "Default")
      (node (ref "R182") (pin "2") (pinfunction "2_2") (pintype "passive"))
      (node (ref "R184") (pin "1") (pinfunction "1_1") (pintype "passive"))
    )
    (net (code "50") (name "Net-(XO1-Output)") (class "Default")
      (node (ref "R171") (pin "2") (pinfunction "2_2") (pintype "passive"))
      (node (ref "XO1") (pin "3") (pinfunction "Output_3") (pintype "output"))
    )
    (net (code "51") (name "Net-(XO1-Vcc)") (class "Default")
      (node (ref "C222") (pin "2") (pinfunction "2_2") (pintype "passive"))
      (node (ref "C223") (pin "2") (pinfunction "2_2") (pintype "passive"))
      (node (ref "C224") (pin "1") (pinfunction "1_1") (pintype "passive"))
      (node (ref "R172") (pin "2") (pinfunction "2_2") (pintype "passive"))
      (node (ref "XO1") (pin "4") (pinfunction "Vcc_4") (pintype "power_in"))
    )
    (net (code "52") (name "Net-(XO2-OUT)") (class "Default")
      (node (ref "R180") (pin "2") (pinfunction "2_2") (pintype "passive"))
      (node (ref "XO2") (pin "4") (pinfunction "OUT_4") (pintype "passive"))
      (node (ref "XO3") (pin "3") (pinfunction "OUT_3") (pintype "passive"))
    )
    (net (code "53") (name "Net-(XO2-TRI-ST.)") (class "Default")
      (node (ref "R179") (pin "1") (pinfunction "1_1") (pintype "passive"))
      (node (ref "XO2") (pin "6") (pinfunction "TRI-ST._6") (pintype "passive"))
    )
    (net (code "54") (name "Net-(XO2-VDD)") (class "Default")
      (node (ref "C240") (pin "2") (pinfunction "2_2") (pintype "passive"))
      (node (ref "C241") (pin "2") (pinfunction "2_2") (pintype "passive"))
      (node (ref "R179") (pin "2") (pinfunction "2_2") (pintype "passive"))
      (node (ref "R181") (pin "1") (pinfunction "1_1") (pintype "passive"))
      (node (ref "XO2") (pin "5") (pinfunction "VDD_5") (pintype "passive"))
      (node (ref "XO3") (pin "4") (pinfunction "VDD_4") (pintype "passive"))
    )
    (net (code "55") (name "Net-(XO4-RF_OUT)") (class "Default")
      (node (ref "R183") (pin "1") (pinfunction "1_1") (pintype "passive"))
      (node (ref "XO4") (pin "6") (pinfunction "RF_OUT_6") (pintype "output"))
    )
    (net (code "56") (name "Net-(XO4-VCC)") (class "Default")
      (node (ref "C242") (pin "2") (pinfunction "2_2") (pintype "passive"))
      (node (ref "C243") (pin "2") (pinfunction "2_2") (pintype "passive"))
      (node (ref "R184") (pin "2") (pinfunction "2_2") (pintype "passive"))
      (node (ref "XO4") (pin "9") (pinfunction "VCC_9") (pintype "power_in"))
    )
    (net (code "57") (name "Net-(XO4-VC_FILTER)") (class "Default")
      (node (ref "C244") (pin "2") (pinfunction "2_2") (pintype "passive"))
      (node (ref "XO4") (pin "7") (pinfunction "VC_FILTER_7") (pintype "input"))
    )
    (net (code "58") (name "VCC1P8") (class "Default")
      (node (ref "FR44") (pin "1") (pinfunction "1_1") (pintype "passive"))
    )
    (net (code "59") (name "VCC2P5") (class "Default")
      (node (ref "R195") (pin "2") (pinfunction "2_2") (pintype "passive"))
    )
    (net (code "60") (name "VCC3P3_CLK") (class "Default")
      (node (ref "C245") (pin "2") (pinfunction "2_2") (pintype "passive"))
      (node (ref "C254") (pin "1") (pinfunction "1_1") (pintype "passive"))
      (node (ref "C255") (pin "1") (pinfunction "1_1") (pintype "passive"))
      (node (ref "FR41") (pin "1") (pinfunction "1_1") (pintype "passive"))
      (node (ref "FR42") (pin "1") (pinfunction "1_1") (pintype "passive"))
      (node (ref "FR43") (pin "1") (pinfunction "1_1") (pintype "passive"))
      (node (ref "FR45") (pin "1") (pinfunction "1_1") (pintype "passive"))
      (node (ref "FR46") (pin "2") (pinfunction "2_2") (pintype "passive"))
      (node (ref "IC32") (pin "16") (pinfunction "DVdd_16") (pintype "passive"))
      (node (ref "IC32") (pin "17") (pinfunction "DVdd_17") (pintype "passive"))
      (node (ref "R187") (pin "2") (pinfunction "2_2") (pintype "passive"))
      (node (ref "R190") (pin "2") (pinfunction "2_2") (pintype "passive"))
    )
    (net (code "61") (name "VCC3P3_LMK") (class "Default")
      (node (ref "C233") (pin "2") (pinfunction "2_2") (pintype "passive"))
      (node (ref "C234") (pin "2") (pinfunction "2_2") (pintype "passive"))
      (node (ref "C235") (pin "2") (pinfunction "2_2") (pintype "passive"))
      (node (ref "C236") (pin "2") (pinfunction "2_2") (pintype "passive"))
      (node (ref "FR43") (pin "2") (pinfunction "2_2") (pintype "passive"))
      (node (ref "IC30") (pin "23") (pinfunction "Vdd_23") (pintype "passive"))
      (node (ref "IC30") (pin "8") (pinfunction "Vdd_8") (pintype "passive"))
      (node (ref "R170") (pin "2") (pinfunction "2_2") (pintype "passive"))
    )
    (net (code "62") (name "VCC3P3_LMK2") (class "Default")
      (node (ref "C228") (pin "2") (pinfunction "2_2") (pintype "passive"))
      (node (ref "C229") (pin "2") (pinfunction "2_2") (pintype "passive"))
      (node (ref "C230") (pin "2") (pinfunction "2_2") (pintype "passive"))
      (node (ref "C231") (pin "2") (pinfunction "2_2") (pintype "passive"))
      (node (ref "FR42") (pin "2") (pinfunction "2_2") (pintype "passive"))
      (node (ref "IC30") (pin "14") (pinfunction "Vddo_14") (pintype "passive"))
      (node (ref "IC30") (pin "18") (pinfunction "Vddo_18") (pintype "passive"))
    )
    (net (code "63") (name "unconnected-(IC30-OSCin-Pad9)") (class "Default")
      (node (ref "IC30") (pin "9") (pinfunction "OSCin_9") (pintype "passive+no_connect"))
    )
    (net (code "64") (name "unconnected-(IC30-OSCout-Pad10)") (class "Default")
      (node (ref "IC30") (pin "10") (pinfunction "OSCout_10") (pintype "passive+no_connect"))
    )
    (net (code "65") (name "unconnected-(XO2-T.S.-Pad3)") (class "Default")
      (node (ref "XO2") (pin "3") (pinfunction "T.S._3") (pintype "passive+no_connect"))
    )
    (net (code "66") (name "unconnected-(XO4-NC-Pad2)") (class "Default")
      (node (ref "XO4") (pin "2") (pinfunction "NC_2") (pintype "passive+no_connect"))
    )
    (net (code "67") (name "unconnected-(XO4-NC-Pad3)") (class "Default")
      (node (ref "XO4") (pin "3") (pinfunction "NC_3") (pintype "passive+no_connect"))
    )
    (net (code "68") (name "unconnected-(XO4-NC-Pad5)") (class "Default")
      (node (ref "XO4") (pin "5") (pinfunction "NC_5") (pintype "passive+no_connect"))
    )
    (net (code "69") (name "unconnected-(XO4-NC-Pad8)") (class "Default")
      (node (ref "XO4") (pin "8") (pinfunction "NC_8") (pintype "passive+no_connect"))
    )
    (net (code "70") (name "unconnected-(XO4-NC-Pad10)") (class "Default")
      (node (ref "XO4") (pin "10") (pinfunction "NC_10") (pintype "passive+no_connect"))
    )
  )
)
